# S7CAS-PLEIADES-CARTE-MERE_P01_FPGA-BANK5.net
KiCad netlist of a schematic drawn in Altium Designer
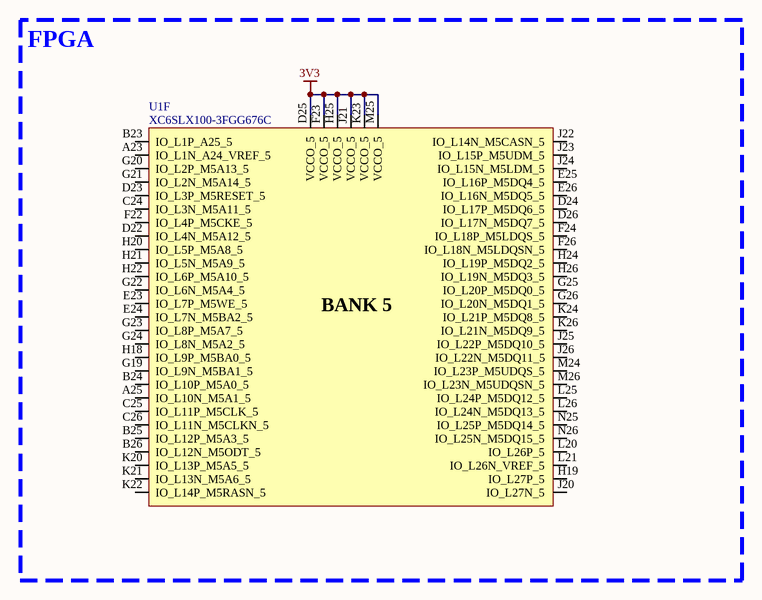
[diagram p0: S7CAS-PLEIADES-CARTE-MERE_P01_FPGA-BANK5.SchDoc]

(export (version "E")
  (design (tool "Eeschema 10.0.6"))
  (components
    (comp (ref "U1")
      (value "XC6SLX100-3FGG676C")
      (footprint "FPGA_XILINX_FGG676")
      (description "FPGA - XILINX SPARTAN 6 480 I/O - BGA-676")
      (fields
        (field (name "VOLTAGE") "1.14 V ~ 1.26 V")
        (field (name "MFG") "Xilinx")
        (field (name "CREATEDBY") "Jonathan Bouchard")
      )
      (libsource (lib "s7cas_lib2023") (part "FPGA_XC6SLX100-3FGG676C"))
    )
  )
  (nets
    (net (code "1") (name "3V3") (class "Default")
      (node (ref "U1") (pin "D25") (pinfunction "VCCO_5_D25") (pintype "passive"))
      (node (ref "U1") (pin "F23") (pinfunction "VCCO_5_F23") (pintype "passive"))
      (node (ref "U1") (pin "H25") (pinfunction "VCCO_5_H25") (pintype "passive"))
      (node (ref "U1") (pin "J21") (pinfunction "VCCO_5_J21") (pintype "passive"))
      (node (ref "U1") (pin "K23") (pinfunction "VCCO_5_K23") (pintype "passive"))
      (node (ref "U1") (pin "M25") (pinfunction "VCCO_5_M25") (pintype "passive"))
    )
    (net (code "2") (name "unconnected-(U1F-IO_L1N_A24_VREF_5-PadA23)") (class "Default")
      (node (ref "U1") (pin "A23") (pinfunction "IO_L1N_A24_VREF_5_A23") (pintype "passive"))
    )
    (net (code "3") (name "unconnected-(U1F-IO_L1P_A25_5-PadB23)") (class "Default")
      (node (ref "U1") (pin "B23") (pinfunction "IO_L1P_A25_5_B23") (pintype "passive"))
    )
    (net (code "4") (name "unconnected-(U1F-IO_L2N_M5A14_5-PadG21)") (class "Default")
      (node (ref "U1") (pin "G21") (pinfunction "IO_L2N_M5A14_5_G21") (pintype "passive"))
    )
    (net (code "5") (name "unconnected-(U1F-IO_L2P_M5A13_5-PadG20)") (class "Default")
      (node (ref "U1") (pin "G20") (pinfunction "IO_L2P_M5A13_5_G20") (pintype "passive"))
    )
    (net (code "6") (name "unconnected-(U1F-IO_L3N_M5A11_5-PadC24)") (class "Default")
      (node (ref "U1") (pin "C24") (pinfunction "IO_L3N_M5A11_5_C24") (pintype "passive"))
    )
    (net (code "7") (name "unconnected-(U1F-IO_L3P_M5RESET_5-PadD23)") (class "Default")
      (node (ref "U1") (pin "D23") (pinfunction "IO_L3P_M5RESET_5_D23") (pintype "passive"))
    )
    (net (code "8") (name "unconnected-(U1F-IO_L4N_M5A12_5-PadD22)") (class "Default")
      (node (ref "U1") (pin "D22") (pinfunction "IO_L4N_M5A12_5_D22") (pintype "passive"))
    )
    (net (code "9") (name "unconnected-(U1F-IO_L4P_M5CKE_5-PadF22)") (class "Default")
      (node (ref "U1") (pin "F22") (pinfunction "IO_L4P_M5CKE_5_F22") (pintype "passive"))
    )
    (net (code "10") (name "unconnected-(U1F-IO_L5N_M5A9_5-PadH21)") (class "Default")
      (node (ref "U1") (pin "H21") (pinfunction "IO_L5N_M5A9_5_H21") (pintype "passive"))
    )
    (net (code "11") (name "unconnected-(U1F-IO_L5P_M5A8_5-PadH20)") (class "Default")
      (node (ref "U1") (pin "H20") (pinfunction "IO_L5P_M5A8_5_H20") (pintype "passive"))
    )
    (net (code "12") (name "unconnected-(U1F-IO_L6N_M5A4_5-PadG22)") (class "Default")
      (node (ref "U1") (pin "G22") (pinfunction "IO_L6N_M5A4_5_G22") (pintype "passive"))
    )
    (net (code "13") (name "unconnected-(U1F-IO_L6P_M5A10_5-PadH22)") (class "Default")
      (node (ref "U1") (pin "H22") (pinfunction "IO_L6P_M5A10_5_H22") (pintype "passive"))
    )
    (net (code "14") (name "unconnected-(U1F-IO_L7N_M5BA2_5-PadE24)") (class "Default")
      (node (ref "U1") (pin "E24") (pinfunction "IO_L7N_M5BA2_5_E24") (pintype "passive"))
    )
    (net (code "15") (name "unconnected-(U1F-IO_L7P_M5WE_5-PadE23)") (class "Default")
      (node (ref "U1") (pin "E23") (pinfunction "IO_L7P_M5WE_5_E23") (pintype "passive"))
    )
    (net (code "16") (name "unconnected-(U1F-IO_L8N_M5A2_5-PadG24)") (class "Default")
      (node (ref "U1") (pin "G24") (pinfunction "IO_L8N_M5A2_5_G24") (pintype "passive"))
    )
    (net (code "17") (name "unconnected-(U1F-IO_L8P_M5A7_5-PadG23)") (class "Default")
      (node (ref "U1") (pin "G23") (pinfunction "IO_L8P_M5A7_5_G23") (pintype "passive"))
    )
    (net (code "18") (name "unconnected-(U1F-IO_L9N_M5BA1_5-PadG19)") (class "Default")
      (node (ref "U1") (pin "G19") (pinfunction "IO_L9N_M5BA1_5_G19") (pintype "passive"))
    )
    (net (code "19") (name "unconnected-(U1F-IO_L9P_M5BA0_5-PadH18)") (class "Default")
      (node (ref "U1") (pin "H18") (pinfunction "IO_L9P_M5BA0_5_H18") (pintype "passive"))
    )
    (net (code "20") (name "unconnected-(U1F-IO_L10N_M5A1_5-PadA25)") (class "Default")
      (node (ref "U1") (pin "A25") (pinfunction "IO_L10N_M5A1_5_A25") (pintype "passive"))
    )
    (net (code "21") (name "unconnected-(U1F-IO_L10P_M5A0_5-PadB24)") (class "Default")
      (node (ref "U1") (pin "B24") (pinfunction "IO_L10P_M5A0_5_B24") (pintype "passive"))
    )
    (net (code "22") (name "unconnected-(U1F-IO_L11N_M5CLKN_5-PadC26)") (class "Default")
      (node (ref "U1") (pin "C26") (pinfunction "IO_L11N_M5CLKN_5_C26") (pintype "passive"))
    )
    (net (code "23") (name "unconnected-(U1F-IO_L11P_M5CLK_5-PadC25)") (class "Default")
      (node (ref "U1") (pin "C25") (pinfunction "IO_L11P_M5CLK_5_C25") (pintype "passive"))
    )
    (net (code "24") (name "unconnected-(U1F-IO_L12N_M5ODT_5-PadB26)") (class "Default")
      (node (ref "U1") (pin "B26") (pinfunction "IO_L12N_M5ODT_5_B26") (pintype "passive"))
    )
    (net (code "25") (name "unconnected-(U1F-IO_L12P_M5A3_5-PadB25)") (class "Default")
      (node (ref "U1") (pin "B25") (pinfunction "IO_L12P_M5A3_5_B25") (pintype "passive"))
    )
    (net (code "26") (name "unconnected-(U1F-IO_L13N_M5A6_5-PadK21)") (class "Default")
      (node (ref "U1") (pin "K21") (pinfunction "IO_L13N_M5A6_5_K21") (pintype "passive"))
    )
    (net (code "27") (name "unconnected-(U1F-IO_L13P_M5A5_5-PadK20)") (class "Default")
      (node (ref "U1") (pin "K20") (pinfunction "IO_L13P_M5A5_5_K20") (pintype "passive"))
    )
    (net (code "28") (name "unconnected-(U1F-IO_L14N_M5CASN_5-PadJ22)") (class "Default")
      (node (ref "U1") (pin "J22") (pinfunction "IO_L14N_M5CASN_5_J22") (pintype "passive"))
    )
    (net (code "29") (name "unconnected-(U1F-IO_L14P_M5RASN_5-PadK22)") (class "Default")
      (node (ref "U1") (pin "K22") (pinfunction "IO_L14P_M5RASN_5_K22") (pintype "passive"))
    )
    (net (code "30") (name "unconnected-(U1F-IO_L15N_M5LDM_5-PadJ24)") (class "Default")
      (node (ref "U1") (pin "J24") (pinfunction "IO_L15N_M5LDM_5_J24") (pintype "passive"))
    )
    (net (code "31") (name "unconnected-(U1F-IO_L15P_M5UDM_5-PadJ23)") (class "Default")
      (node (ref "U1") (pin "J23") (pinfunction "IO_L15P_M5UDM_5_J23") (pintype "passive"))
    )
    (net (code "32") (name "unconnected-(U1F-IO_L16N_M5DQ5_5-PadE26)") (class "Default")
      (node (ref "U1") (pin "E26") (pinfunction "IO_L16N_M5DQ5_5_E26") (pintype "passive"))
    )
    (net (code "33") (name "unconnected-(U1F-IO_L16P_M5DQ4_5-PadE25)") (class "Default")
      (node (ref "U1") (pin "E25") (pinfunction "IO_L16P_M5DQ4_5_E25") (pintype "passive"))
    )
    (net (code "34") (name "unconnected-(U1F-IO_L17N_M5DQ7_5-PadD26)") (class "Default")
      (node (ref "U1") (pin "D26") (pinfunction "IO_L17N_M5DQ7_5_D26") (pintype "passive"))
    )
    (net (code "35") (name "unconnected-(U1F-IO_L17P_M5DQ6_5-PadD24)") (class "Default")
      (node (ref "U1") (pin "D24") (pinfunction "IO_L17P_M5DQ6_5_D24") (pintype "passive"))
    )
    (net (code "36") (name "unconnected-(U1F-IO_L18N_M5LDQSN_5-PadF26)") (class "Default")
      (node (ref "U1") (pin "F26") (pinfunction "IO_L18N_M5LDQSN_5_F26") (pintype "passive"))
    )
    (net (code "37") (name "unconnected-(U1F-IO_L18P_M5LDQS_5-PadF24)") (class "Default")
      (node (ref "U1") (pin "F24") (pinfunction "IO_L18P_M5LDQS_5_F24") (pintype "passive"))
    )
    (net (code "38") (name "unconnected-(U1F-IO_L19N_M5DQ3_5-PadH26)") (class "Default")
      (node (ref "U1") (pin "H26") (pinfunction "IO_L19N_M5DQ3_5_H26") (pintype "passive"))
    )
    (net (code "39") (name "unconnected-(U1F-IO_L19P_M5DQ2_5-PadH24)") (class "Default")
      (node (ref "U1") (pin "H24") (pinfunction "IO_L19P_M5DQ2_5_H24") (pintype "passive"))
    )
    (net (code "40") (name "unconnected-(U1F-IO_L20N_M5DQ1_5-PadG26)") (class "Default")
      (node (ref "U1") (pin "G26") (pinfunction "IO_L20N_M5DQ1_5_G26") (pintype "passive"))
    )
    (net (code "41") (name "unconnected-(U1F-IO_L20P_M5DQ0_5-PadG25)") (class "Default")
      (node (ref "U1") (pin "G25") (pinfunction "IO_L20P_M5DQ0_5_G25") (pintype "passive"))
    )
    (net (code "42") (name "unconnected-(U1F-IO_L21N_M5DQ9_5-PadK26)") (class "Default")
      (node (ref "U1") (pin "K26") (pinfunction "IO_L21N_M5DQ9_5_K26") (pintype "passive"))
    )
    (net (code "43") (name "unconnected-(U1F-IO_L21P_M5DQ8_5-PadK24)") (class "Default")
      (node (ref "U1") (pin "K24") (pinfunction "IO_L21P_M5DQ8_5_K24") (pintype "passive"))
    )
    (net (code "44") (name "unconnected-(U1F-IO_L22N_M5DQ11_5-PadJ26)") (class "Default")
      (node (ref "U1") (pin "J26") (pinfunction "IO_L22N_M5DQ11_5_J26") (pintype "passive"))
    )
    (net (code "45") (name "unconnected-(U1F-IO_L22P_M5DQ10_5-PadJ25)") (class "Default")
      (node (ref "U1") (pin "J25") (pinfunction "IO_L22P_M5DQ10_5_J25") (pintype "passive"))
    )
    (net (code "46") (name "unconnected-(U1F-IO_L23N_M5UDQSN_5-PadM26)") (class "Default")
      (node (ref "U1") (pin "M26") (pinfunction "IO_L23N_M5UDQSN_5_M26") (pintype "passive"))
    )
    (net (code "47") (name "unconnected-(U1F-IO_L23P_M5UDQS_5-PadM24)") (class "Default")
      (node (ref "U1") (pin "M24") (pinfunction "IO_L23P_M5UDQS_5_M24") (pintype "passive"))
    )
    (net (code "48") (name "unconnected-(U1F-IO_L24N_M5DQ13_5-PadL26)") (class "Default")
      (node (ref "U1") (pin "L26") (pinfunction "IO_L24N_M5DQ13_5_L26") (pintype "passive"))
    )
    (net (code "49") (name "unconnected-(U1F-IO_L24P_M5DQ12_5-PadL25)") (class "Default")
      (node (ref "U1") (pin "L25") (pinfunction "IO_L24P_M5DQ12_5_L25") (pintype "passive"))
    )
    (net (code "50") (name "unconnected-(U1F-IO_L25N_M5DQ15_5-PadN26)") (class "Default")
      (node (ref "U1") (pin "N26") (pinfunction "IO_L25N_M5DQ15_5_N26") (pintype "passive"))
    )
    (net (code "51") (name "unconnected-(U1F-IO_L25P_M5DQ14_5-PadN25)") (class "Default")
      (node (ref "U1") (pin "N25") (pinfunction "IO_L25P_M5DQ14_5_N25") (pintype "passive"))
    )
    (net (code "52") (name "unconnected-(U1F-IO_L26N_VREF_5-PadL21)") (class "Default")
      (node (ref "U1") (pin "L21") (pinfunction "IO_L26N_VREF_5_L21") (pintype "passive"))
    )
    (net (code "53") (name "unconnected-(U1F-IO_L26P_5-PadL20)") (class "Default")
      (node (ref "U1") (pin "L20") (pinfunction "IO_L26P_5_L20") (pintype "passive"))
    )
    (net (code "54") (name "unconnected-(U1F-IO_L27N_5-PadJ20)") (class "Default")
      (node (ref "U1") (pin "J20") (pinfunction "IO_L27N_5_J20") (pintype "passive"))
    )
    (net (code "55") (name "unconnected-(U1F-IO_L27P_5-PadH19)") (class "Default")
      (node (ref "U1") (pin "H19") (pinfunction "IO_L27P_5_H19") (pintype "passive"))
    )
  )
)
